# 3_PressureSensor.net
KiCad netlist of a schematic drawn in Altium Designer
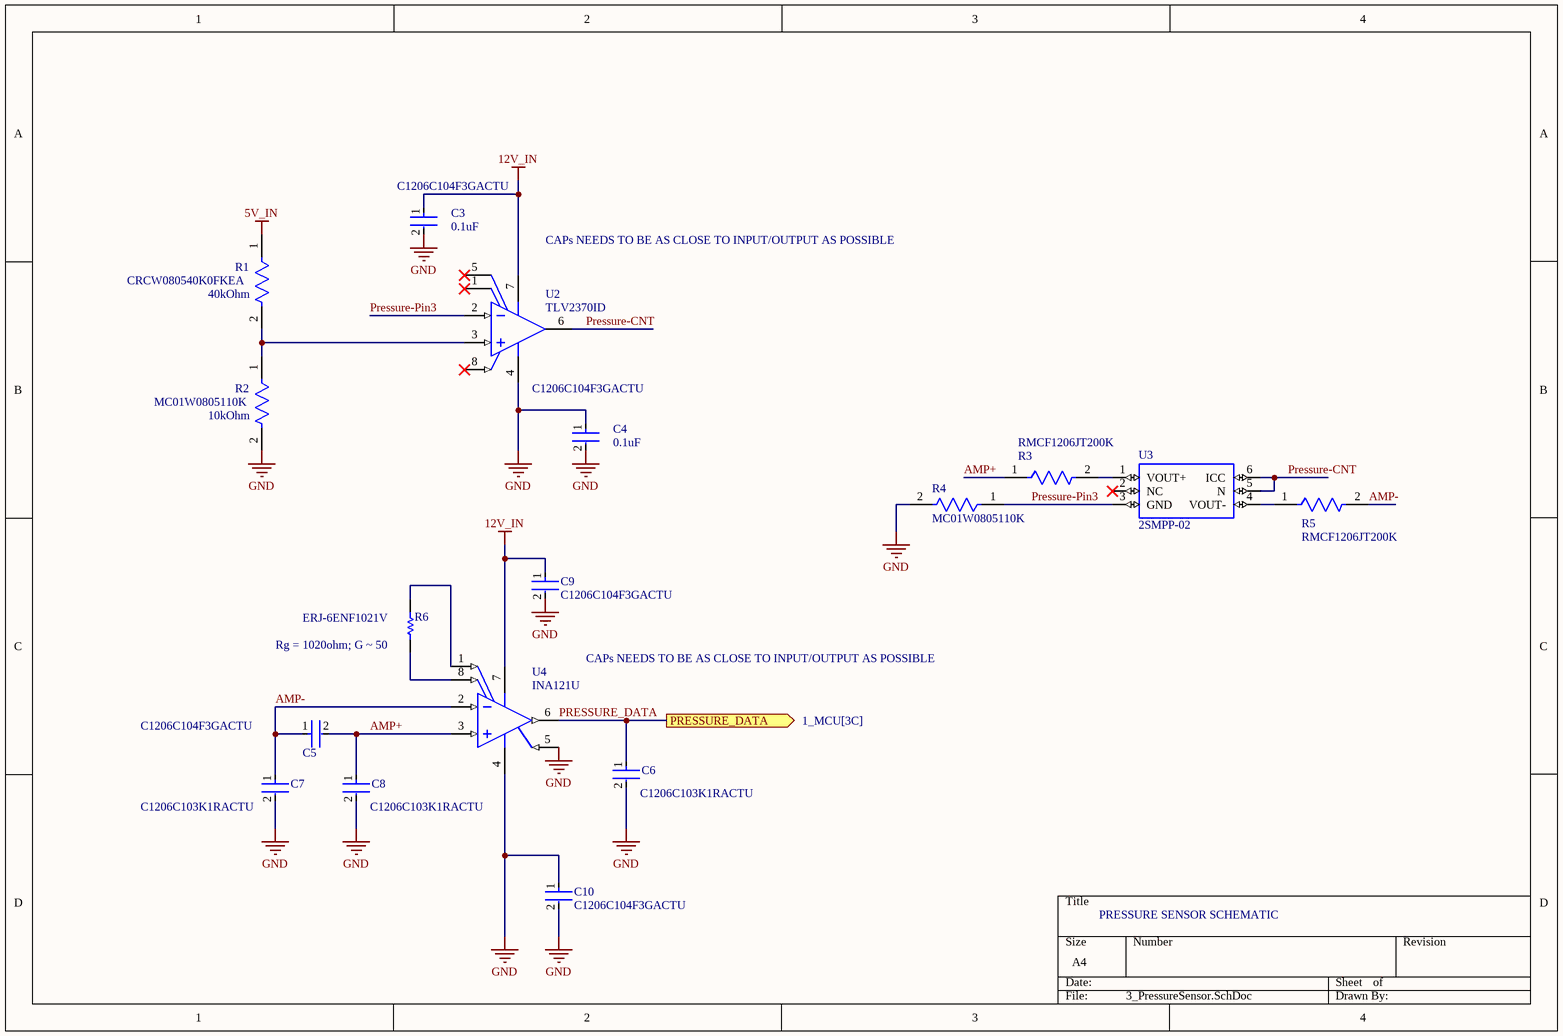
[diagram p0: 3_PressureSensor.SchDoc]

(export (version "E")
  (design (tool "Eeschema 10.0.6"))
  (components
    (comp (ref "C3")
      (value "C1206C104F3GACTU")
      (footprint "FP-C1206C-EB-MFG")
      (description "CAP CER 0.1UF 25V C0G/NP0 1206")
      (fields (field (name "MANUFACTURER") "KEMET") (field (name "TOLERANCE") "0.01"))
      (libsource (lib "Altium Content Vault") (part "b4654b650e69147ec39a6b967a45e02"))
    )
    (comp (ref "C4")
      (value "C1206C104F3GACTU")
      (footprint "FP-C1206C-EB-MFG")
      (description "CAP CER 0.1UF 25V C0G/NP0 1206")
      (fields (field (name "MANUFACTURER") "KEMET") (field (name "TOLERANCE") "0.01"))
      (libsource (lib "Altium Content Vault") (part "b4654b650e69147ec39a6b967a45e02"))
    )
    (comp (ref "C5")
      (value "C1206C104F3GACTU")
      (footprint "FP-C1206C-EB-MFG")
      (description "CAP CER 0.1UF 25V C0G/NP0 1206")
      (fields (field (name "MANUFACTURER") "KEMET") (field (name "TOLERANCE") "0.01"))
      (libsource (lib "Altium Content Vault") (part "b4654b650e69147ec39a6b967a45e02"))
    )
    (comp (ref "C6")
      (value "C1206C103K1RACTU")
      (footprint "FP-C1206C-EB-MFG")
      (description "Cap Ceramic 0.01uF 100V X7R 10% SMD 1206 125°C Plastic T/R")
      (fields
        (field (name "MANUFACTURER") "KEMET")
        (field (name "OCTOPART") "https://octopart.com/c1206c103k1ractu-kemet-117927")
      )
      (libsource (lib "Altium Content Vault") (part "b4654b650e69147ec39a6b967a45e02"))
    )
    (comp (ref "C7")
      (value "C1206C103K1RACTU")
      (footprint "FP-C1206C-EB-MFG")
      (description "Cap Ceramic 0.01uF 100V X7R 10% SMD 1206 125°C Plastic T/R")
      (fields
        (field (name "MANUFACTURER") "KEMET")
        (field (name "OCTOPART") "https://octopart.com/c1206c103k1ractu-kemet-117927")
      )
      (libsource (lib "Altium Content Vault") (part "b4654b650e69147ec39a6b967a45e02"))
    )
    (comp (ref "C8")
      (value "C1206C103K1RACTU")
      (footprint "FP-C1206C-EB-MFG")
      (description "Cap Ceramic 0.01uF 100V X7R 10% SMD 1206 125°C Plastic T/R")
      (fields
        (field (name "MANUFACTURER") "KEMET")
        (field (name "OCTOPART") "https://octopart.com/c1206c103k1ractu-kemet-117927")
      )
      (libsource (lib "Altium Content Vault") (part "b4654b650e69147ec39a6b967a45e02"))
    )
    (comp (ref "C9")
      (value "C1206C104F3GACTU")
      (footprint "FP-C1206C-EB-MFG")
      (description "CAP CER 0.1UF 25V C0G/NP0 1206")
      (fields (field (name "MANUFACTURER") "KEMET") (field (name "TOLERANCE") "0.01"))
      (libsource (lib "Altium Content Vault") (part "b4654b650e69147ec39a6b967a45e02"))
    )
    (comp (ref "C10")
      (value "C1206C104F3GACTU")
      (footprint "FP-C1206C-EB-MFG")
      (description "CAP CER 0.1UF 25V C0G/NP0 1206")
      (fields (field (name "MANUFACTURER") "KEMET") (field (name "TOLERANCE") "0.01"))
      (libsource (lib "Altium Content Vault") (part "b4654b650e69147ec39a6b967a45e02"))
    )
    (comp (ref "R1")
      (value "CRCW080540K0FKEA")
      (footprint "FP-CRCW0805-e3-MFG")
      (description "RES Thick Film, 40kΩ, 1%, 0.125W, 100ppm/°C, 0805")
      (fields (field (name "TOLERANCE") "1%"))
      (libsource (lib "Altium Content Vault") (part "1029c3af85768c4190bb7ad29bc67b5"))
    )
    (comp (ref "R2")
      (value "MC01W0805110K")
      (footprint "FP-MC01W0805-IPC_C")
      (description "Resistor, 10K, 0.1W, 1%, 0805, Reel")
      (fields (field (name "TOLERANCE") "1%"))
      (libsource (lib "Altium Content Vault") (part "1029c3af85768c4190bb7ad29bc67b5"))
    )
    (comp (ref "R3")
      (value "RMCF1206JT200K")
      (footprint "FP-RMCF1206-IPC_C")
      (description "200kΩ ±5% 0.25W 1206 Thick Film Chip Resistor AEC-Q200 compliant")
      (fields (field (name "TOLERANCE") "5%"))
      (libsource (lib "Altium Content Vault") (part "1029c3af85768c4190bb7ad29bc67b5"))
    )
    (comp (ref "R4")
      (value "MC01W0805110K")
      (footprint "FP-MC01W0805-IPC_C")
      (description "Resistor, 10K, 0.1W, 1%, 0805, Reel")
      (fields (field (name "TOLERANCE") "1%"))
      (libsource (lib "Altium Content Vault") (part "1029c3af85768c4190bb7ad29bc67b5"))
    )
    (comp (ref "R5")
      (value "RMCF1206JT200K")
      (footprint "FP-RMCF1206-IPC_C")
      (description "200kΩ ±5% 0.25W 1206 Thick Film Chip Resistor AEC-Q200 compliant")
      (fields (field (name "TOLERANCE") "5%"))
      (libsource (lib "Altium Content Vault") (part "1029c3af85768c4190bb7ad29bc67b5"))
    )
    (comp (ref "R6")
      (value "ERJ-6ENF1021V")
      (footprint "RESC2013X70X40ML20T20")
      (fields (field (name "MANUFACTURER") "Panasonic"))
      (libsource (lib "Altium Content Vault") (part "RES"))
    )
    (comp (ref "U2")
      (value "TLV2370ID")
      (footprint "D0008A_L")
      (fields (field (name "MANUFACTURER") "Texas Instruments"))
      (libsource (lib "Altium Content Vault") (part "TI-TLV2X70_2760_2780_4110-8"))
    )
    (comp (ref "U3")
      (value "2SMPP-02")
      (footprint "2SMPP_PAC")
      (description "Pressure Sensor 5.37PSI _37kPa_ Vented Gauge Male - 0.1 _2.59mm_ Tube 0 mV ~ 31 mV 6-SMD Module")
      (fields (field (name "MF") "Omron"))
      (libsource (lib "McMaster University") (part "2SMPP-02"))
    )
    (comp (ref "U4")
      (value "INA121U")
      (footprint "D0008A_M")
      (fields (field (name "MANUFACTURER") "Texas Instruments"))
      (libsource (lib "Altium Content Vault") (part "TI-INA1XX-8"))
    )
  )
  (nets
    (net (code "1") (name "/AMP+") (class "Default")
      (node (ref "C5") (pin "2") (pinfunction "2_2") (pintype "passive"))
      (node (ref "C8") (pin "1") (pinfunction "1_1") (pintype "passive"))
      (node (ref "R3") (pin "1") (pinfunction "1_1") (pintype "passive"))
      (node (ref "U4") (pin "3") (pinfunction "VIN+_3") (pintype "input"))
    )
    (net (code "2") (name "/AMP-") (class "Default")
      (node (ref "C5") (pin "1") (pinfunction "1_1") (pintype "passive"))
      (node (ref "C7") (pin "1") (pinfunction "1_1") (pintype "passive"))
      (node (ref "R5") (pin "2") (pinfunction "2_2") (pintype "passive"))
      (node (ref "U4") (pin "2") (pinfunction "VIN-_2") (pintype "input"))
    )
    (net (code "3") (name "/PRESSURE_DATA") (class "Default")
      (node (ref "C6") (pin "1") (pinfunction "1_1") (pintype "passive"))
      (node (ref "U4") (pin "6") (pinfunction "VO_6") (pintype "output"))
    )
    (net (code "4") (name "/Pressure-CNT") (class "Default")
      (node (ref "U2") (pin "6") (pinfunction "OUT_6") (pintype "tri_state"))
      (node (ref "U3") (pin "5") (pinfunction "N_5") (pintype "bidirectional"))
      (node (ref "U3") (pin "6") (pinfunction "ICC_6") (pintype "bidirectional"))
    )
    (net (code "5") (name "/Pressure-Pin3") (class "Default")
      (node (ref "R4") (pin "1") (pinfunction "1_1") (pintype "passive"))
      (node (ref "U2") (pin "2") (pinfunction "IN-_2") (pintype "input"))
      (node (ref "U3") (pin "3") (pinfunction "GND_3") (pintype "bidirectional"))
    )
    (net (code "6") (name "5V_IN") (class "Default")
      (node (ref "R1") (pin "1") (pinfunction "1_1") (pintype "passive"))
    )
    (net (code "7") (name "12V_IN") (class "Default")
      (node (ref "C3") (pin "1") (pinfunction "1_1") (pintype "passive"))
      (node (ref "C9") (pin "1") (pinfunction "1_1") (pintype "passive"))
      (node (ref "U2") (pin "7") (pinfunction "VDD_7") (pintype "power_in"))
      (node (ref "U4") (pin "7") (pinfunction "V+_7") (pintype "power_in"))
    )
    (net (code "8") (name "GND") (class "Default")
      (node (ref "C10") (pin "1") (pinfunction "1_1") (pintype "passive"))
      (node (ref "C10") (pin "2") (pinfunction "2_2") (pintype "passive"))
      (node (ref "C3") (pin "2") (pinfunction "2_2") (pintype "passive"))
      (node (ref "C4") (pin "1") (pinfunction "1_1") (pintype "passive"))
      (node (ref "C4") (pin "2") (pinfunction "2_2") (pintype "passive"))
      (node (ref "C6") (pin "2") (pinfunction "2_2") (pintype "passive"))
      (node (ref "C7") (pin "2") (pinfunction "2_2") (pintype "passive"))
      (node (ref "C8") (pin "2") (pinfunction "2_2") (pintype "passive"))
      (node (ref "C9") (pin "2") (pinfunction "2_2") (pintype "passive"))
      (node (ref "R2") (pin "2") (pinfunction "2_2") (pintype "passive"))
      (node (ref "R4") (pin "2") (pinfunction "2_2") (pintype "passive"))
      (node (ref "U2") (pin "4") (pinfunction "GND_4") (pintype "power_in"))
      (node (ref "U4") (pin "4") (pinfunction "V-_4") (pintype "power_in"))
      (node (ref "U4") (pin "5") (pinfunction "REF_5") (pintype "input"))
    )
    (net (code "9") (name "Net-(R6-Pad1)") (class "Default")
      (node (ref "R6") (pin "1") (pinfunction "1_1") (pintype "passive"))
      (node (ref "U4") (pin "1") (pinfunction "RG_1") (pintype "input"))
    )
    (net (code "10") (name "Net-(R6-Pad2)") (class "Default")
      (node (ref "R6") (pin "2") (pinfunction "2_2") (pintype "passive"))
      (node (ref "U4") (pin "8") (pinfunction "RG_8") (pintype "input"))
    )
    (net (code "11") (name "Net-(U2-IN+)") (class "Default")
      (node (ref "R1") (pin "2") (pinfunction "2_2") (pintype "passive"))
      (node (ref "R2") (pin "1") (pinfunction "1_1") (pintype "passive"))
      (node (ref "U2") (pin "3") (pinfunction "IN+_3") (pintype "input"))
    )
    (net (code "12") (name "Net-(U3-VOUT+)") (class "Default")
      (node (ref "R3") (pin "2") (pinfunction "2_2") (pintype "passive"))
      (node (ref "U3") (pin "1") (pinfunction "VOUT+_1") (pintype "bidirectional"))
    )
    (net (code "13") (name "Net-(U3-VOUT-)") (class "Default")
      (node (ref "R5") (pin "1") (pinfunction "1_1") (pintype "passive"))
      (node (ref "U3") (pin "4") (pinfunction "VOUT-_4") (pintype "bidirectional"))
    )
    (net (code "14") (name "unconnected-(U2-NC-Pad1)") (class "Default")
      (node (ref "U2") (pin "1") (pinfunction "NC_1") (pintype "passive+no_connect"))
    )
    (net (code "15") (name "unconnected-(U2-NC-Pad5)") (class "Default")
      (node (ref "U2") (pin "5") (pinfunction "NC_5") (pintype "passive+no_connect"))
    )
    (net (code "16") (name "unconnected-(U2-~{SHDN}-Pad8)") (class "Default")
      (node (ref "U2") (pin "8") (pinfunction "~{SHDN}_8") (pintype "input+no_connect"))
    )
    (net (code "17") (name "unconnected-(U3-NC-Pad2)") (class "Default")
      (node (ref "U3") (pin "2") (pinfunction "NC_2") (pintype "bidirectional+no_connect"))
    )
  )
)
